# f4mpac.net
KiCad netlist of a schematic drawn in EAGLE
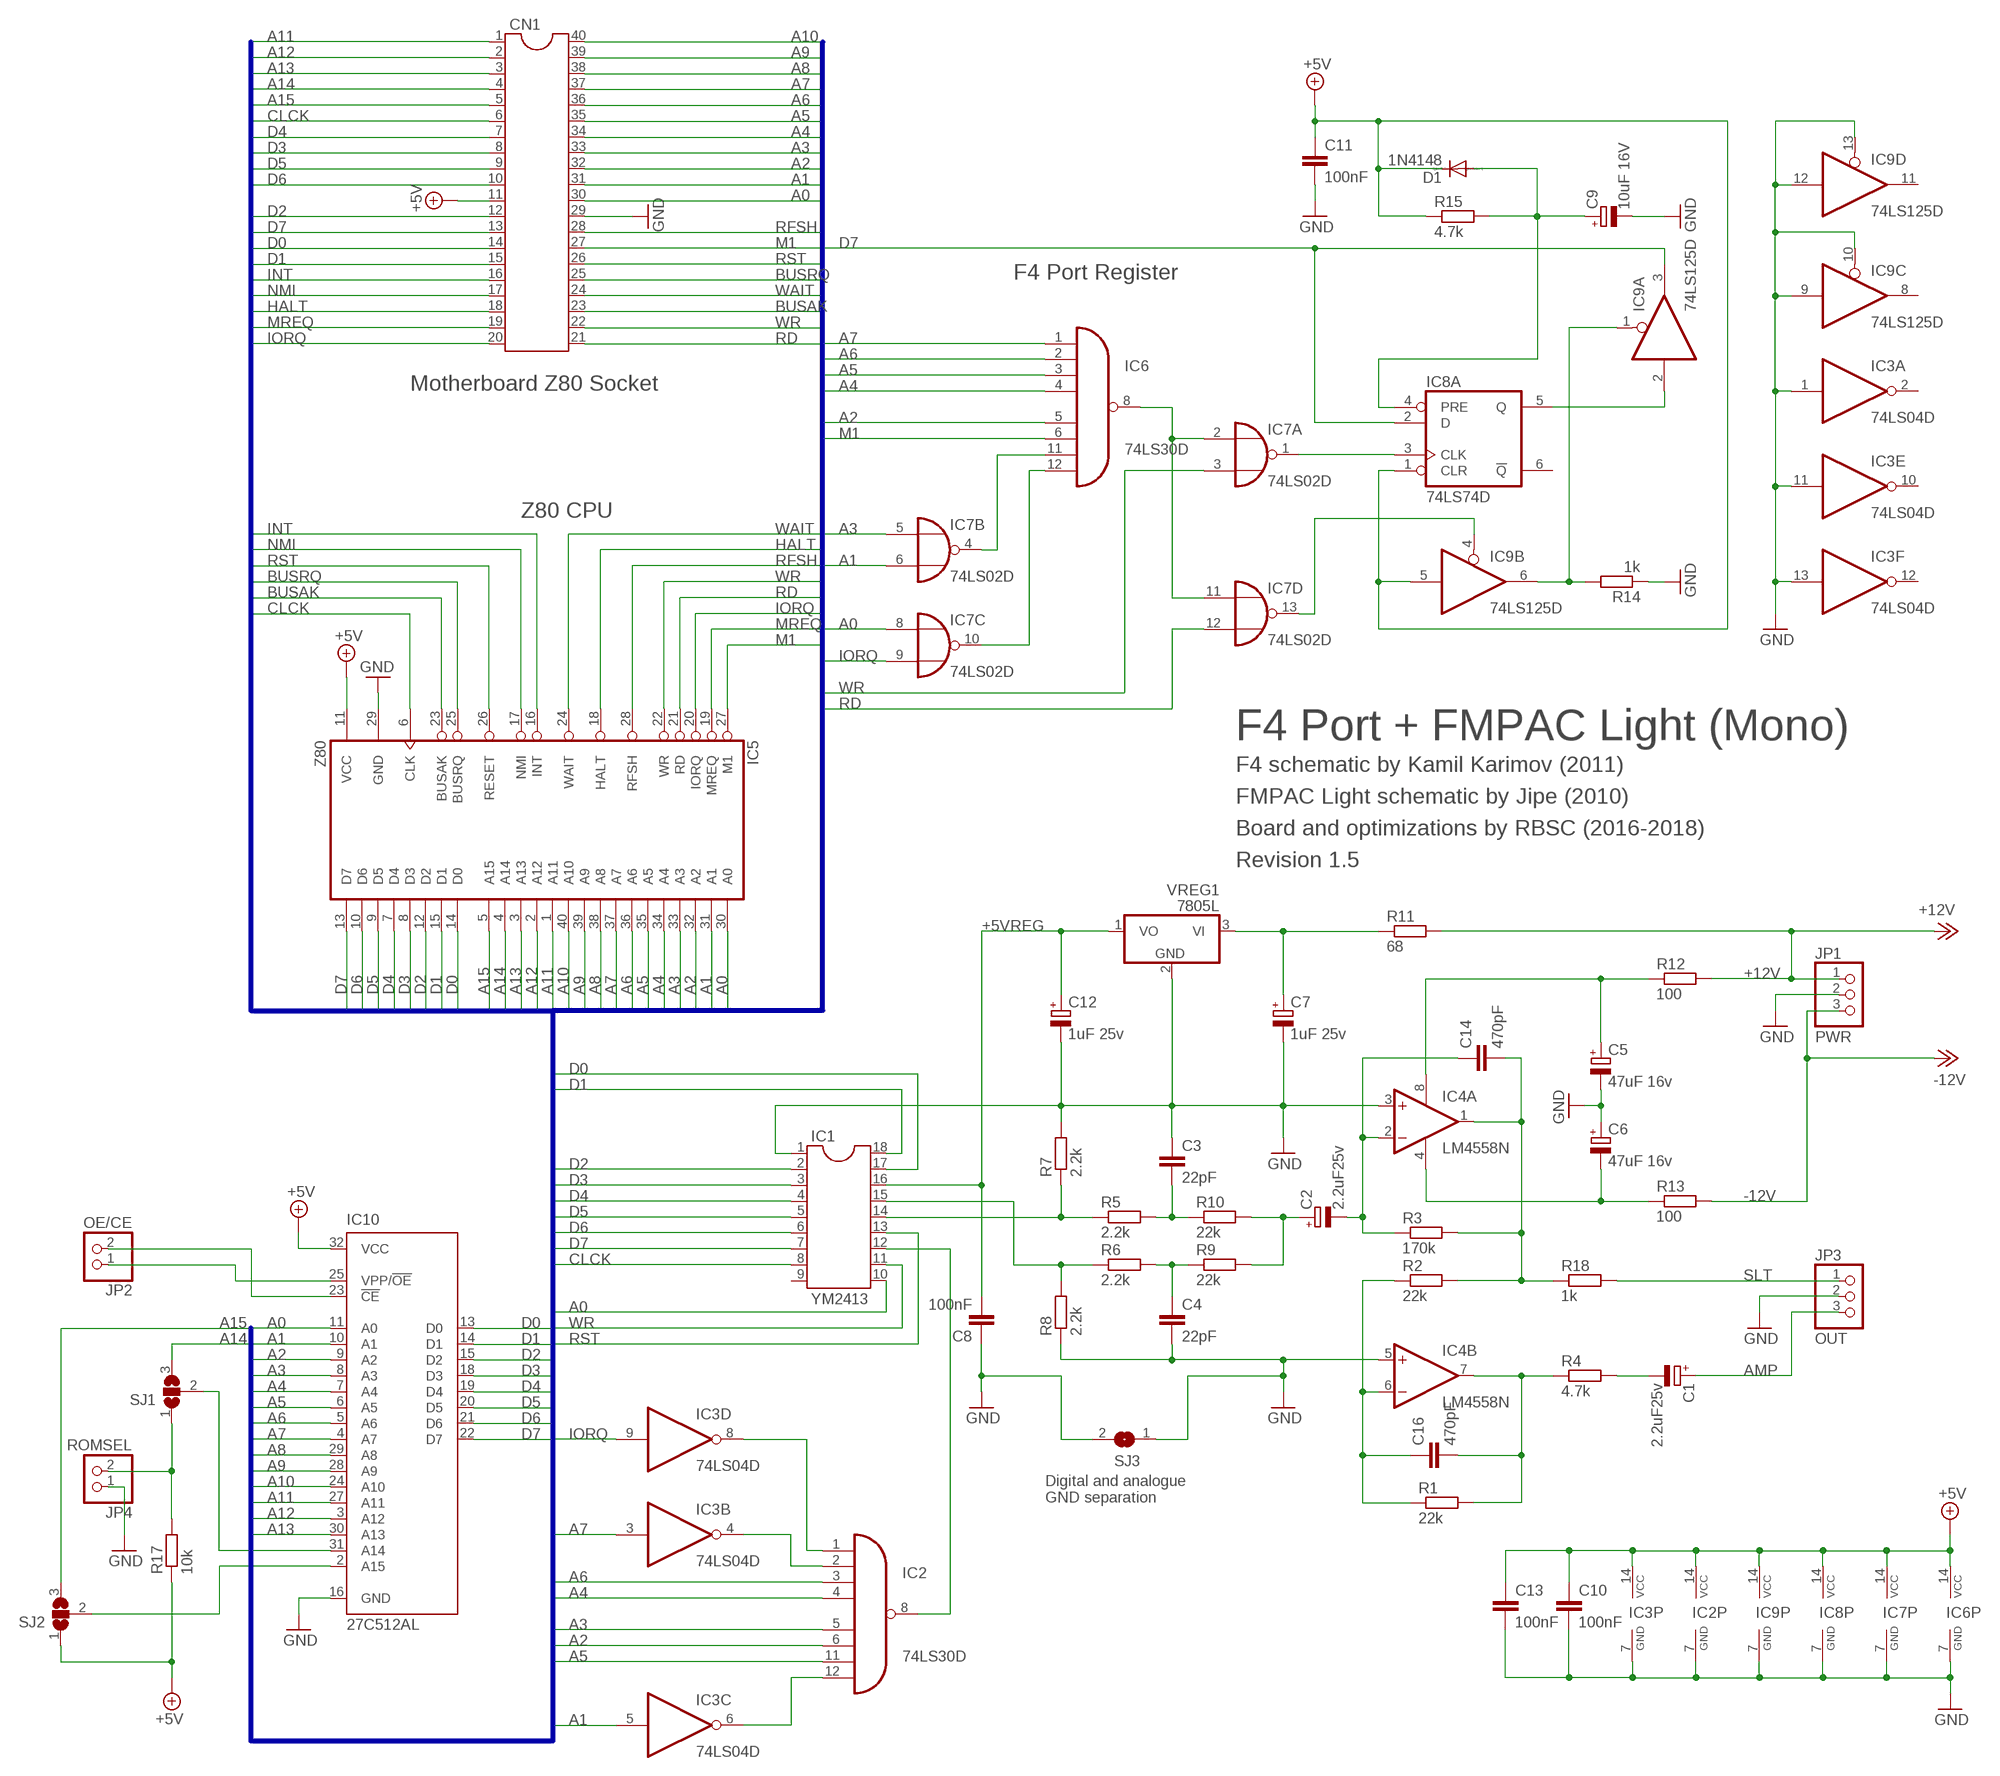
[diagram p0: schematic, sheet 1]

(export (version "E")
  (design (tool "Eeschema 10.0.6"))
  (components
    (comp (ref "C1")
      (value "2.2uF25v")
      (footprint "eagle-import:SMC_B")
      (libsource (lib "eagle-import") (part "CPOL-EUSMCB"))
    )
    (comp (ref "C2")
      (value "2.2uF25v")
      (footprint "eagle-import:SMC_B")
      (libsource (lib "eagle-import") (part "CPOL-EUSMCB"))
    )
    (comp (ref "C3")
      (value "22pF")
      (footprint "eagle-import:C0805")
      (libsource (lib "eagle-import") (part "C-EUC0805"))
    )
    (comp (ref "C4")
      (value "22pF")
      (footprint "eagle-import:C0805")
      (libsource (lib "eagle-import") (part "C-EUC0805"))
    )
    (comp (ref "C5")
      (value "47uF 16v")
      (footprint "eagle-import:SMC_C")
      (libsource (lib "eagle-import") (part "CPOL-EUSMCC"))
    )
    (comp (ref "C6")
      (value "47uF 16v")
      (footprint "eagle-import:SMC_C")
      (libsource (lib "eagle-import") (part "CPOL-EUSMCC"))
    )
    (comp (ref "C7")
      (value "1uF 25v")
      (footprint "eagle-import:SMC_B")
      (libsource (lib "eagle-import") (part "CPOL-EUSMCB"))
    )
    (comp (ref "C8")
      (value "100nF")
      (footprint "eagle-import:C0805")
      (libsource (lib "eagle-import") (part "C-EUC0805"))
    )
    (comp (ref "C9")
      (value "10uF 16V")
      (footprint "eagle-import:SMC_B")
      (libsource (lib "eagle-import") (part "CPOL-EUSMCB"))
    )
    (comp (ref "C10")
      (value "100nF")
      (footprint "eagle-import:C0805")
      (libsource (lib "eagle-import") (part "C-EUC0805"))
    )
    (comp (ref "C11")
      (value "100nF")
      (footprint "eagle-import:C0805")
      (libsource (lib "eagle-import") (part "C-EUC0805"))
    )
    (comp (ref "C12")
      (value "1uF 25v")
      (footprint "eagle-import:SMC_B")
      (libsource (lib "eagle-import") (part "CPOL-EUSMCB"))
    )
    (comp (ref "C13")
      (value "100nF")
      (footprint "eagle-import:C0805")
      (libsource (lib "eagle-import") (part "C-EUC0805"))
    )
    (comp (ref "C14")
      (value "470pF")
      (footprint "eagle-import:C0805")
      (libsource (lib "eagle-import") (part "C-EUC0805"))
    )
    (comp (ref "C16")
      (value "470pF")
      (footprint "eagle-import:C0805")
      (libsource (lib "eagle-import") (part "C-EUC0805"))
    )
    (comp (ref "CN1")
      (value "DIP40 MB CONN")
      (footprint "eagle-import:DIL40")
      (libsource (lib "eagle-import") (part "DIL40"))
    )
    (comp (ref "D1")
      (value "1N4148")
      (footprint "eagle-import:MINIMELF")
      (libsource (lib "eagle-import") (part "DIODE-MINIMELF"))
    )
    (comp (ref "IC1")
      (value "YM2413")
      (footprint "eagle-import:DIL18")
      (libsource (lib "eagle-import") (part "DIL18"))
    )
    (comp (ref "IC2")
      (value "74LS30D")
      (footprint "eagle-import:SO14")
      (libsource (lib "eagle-import") (part "7430DLS"))
    )
    (comp (ref "IC3")
      (value "74LS04D")
      (footprint "eagle-import:SO14")
      (libsource (lib "eagle-import") (part "7404DLS"))
    )
    (comp (ref "IC4")
      (value "LM4558N")
      (footprint "eagle-import:DIL08")
      (libsource (lib "eagle-import") (part "4558NLM"))
    )
    (comp (ref "IC5")
      (value "Z80")
      (footprint "eagle-import:DIL40")
      (libsource (lib "eagle-import") (part "Z80CPU"))
    )
    (comp (ref "IC6")
      (value "74LS30D")
      (footprint "eagle-import:SO14")
      (libsource (lib "eagle-import") (part "7430DLS"))
    )
    (comp (ref "IC7")
      (value "74LS02D")
      (footprint "eagle-import:SO14")
      (libsource (lib "eagle-import") (part "7402DLS"))
    )
    (comp (ref "IC8")
      (value "74LS74D")
      (footprint "eagle-import:SO14")
      (libsource (lib "eagle-import") (part "7474DLS"))
    )
    (comp (ref "IC9")
      (value "74LS125D")
      (footprint "eagle-import:SO14")
      (libsource (lib "eagle-import") (part "74125DLS"))
    )
    (comp (ref "IC10")
      (value "27C512AL")
      (footprint "eagle-import:PLCC-32")
      (fields (field (name "MPN") "M27C512-90C1"))
      (libsource (lib "eagle-import") (part "27512ALC"))
    )
    (comp (ref "JP1")
      (value "PWR")
      (footprint "eagle-import:1X03_90")
      (libsource (lib "eagle-import") (part "PINHD-1X3/90"))
    )
    (comp (ref "JP2")
      (value "OE/CE")
      (footprint "eagle-import:1X02_90")
      (libsource (lib "eagle-import") (part "PINHD-1X2/90"))
    )
    (comp (ref "JP3")
      (value "OUT")
      (footprint "eagle-import:1X03_90")
      (libsource (lib "eagle-import") (part "PINHD-1X3/90"))
    )
    (comp (ref "JP4")
      (value "ROMSEL")
      (footprint "eagle-import:1X02_90")
      (libsource (lib "eagle-import") (part "PINHD-1X2/90"))
    )
    (comp (ref "R1")
      (value "22k")
      (footprint "eagle-import:R0805")
      (libsource (lib "eagle-import") (part "R-EU_R0805"))
    )
    (comp (ref "R2")
      (value "22k")
      (footprint "eagle-import:R0805")
      (libsource (lib "eagle-import") (part "R-EU_R0805"))
    )
    (comp (ref "R3")
      (value "170k")
      (footprint "eagle-import:R0805")
      (libsource (lib "eagle-import") (part "R-EU_R0805"))
    )
    (comp (ref "R4")
      (value "4.7k")
      (footprint "eagle-import:R0805")
      (libsource (lib "eagle-import") (part "R-EU_R0805"))
    )
    (comp (ref "R5")
      (value "2.2k")
      (footprint "eagle-import:R0805")
      (libsource (lib "eagle-import") (part "R-EU_R0805"))
    )
    (comp (ref "R6")
      (value "2.2k")
      (footprint "eagle-import:R0805")
      (libsource (lib "eagle-import") (part "R-EU_R0805"))
    )
    (comp (ref "R7")
      (value "2.2k")
      (footprint "eagle-import:R0805")
      (libsource (lib "eagle-import") (part "R-EU_R0805"))
    )
    (comp (ref "R8")
      (value "2.2k")
      (footprint "eagle-import:R0805")
      (libsource (lib "eagle-import") (part "R-EU_R0805"))
    )
    (comp (ref "R9")
      (value "22k")
      (footprint "eagle-import:R0805")
      (libsource (lib "eagle-import") (part "R-EU_R0805"))
    )
    (comp (ref "R10")
      (value "22k")
      (footprint "eagle-import:R0805")
      (libsource (lib "eagle-import") (part "R-EU_R0805"))
    )
    (comp (ref "R11")
      (value "68")
      (footprint "eagle-import:R0805")
      (libsource (lib "eagle-import") (part "R-EU_R0805"))
    )
    (comp (ref "R12")
      (value "100")
      (footprint "eagle-import:R0805")
      (libsource (lib "eagle-import") (part "R-EU_R0805"))
    )
    (comp (ref "R13")
      (value "100")
      (footprint "eagle-import:R0805")
      (libsource (lib "eagle-import") (part "R-EU_R0805"))
    )
    (comp (ref "R14")
      (value "1k")
      (footprint "eagle-import:R0805")
      (libsource (lib "eagle-import") (part "R-EU_R0805"))
    )
    (comp (ref "R15")
      (value "4.7k")
      (footprint "eagle-import:M0805")
      (libsource (lib "eagle-import") (part "R-EU_M0805"))
    )
    (comp (ref "R17")
      (value "10k")
      (footprint "eagle-import:R0805")
      (libsource (lib "eagle-import") (part "R-EU_R0805"))
    )
    (comp (ref "R18")
      (value "1k")
      (footprint "eagle-import:R0805")
      (libsource (lib "eagle-import") (part "R-EU_R0805"))
    )
    (comp (ref "SJ1")
      (value "SJ2W")
      (footprint "eagle-import:SJ_2")
      (libsource (lib "eagle-import") (part "SJ2W"))
    )
    (comp (ref "SJ2")
      (value "SJ2W")
      (footprint "eagle-import:SJ_2")
      (libsource (lib "eagle-import") (part "SJ2W"))
    )
    (comp (ref "SJ3") (value "SJ") (footprint "eagle-import:SJ") (libsource (lib "eagle-import") (part "SJ")))
    (comp (ref "VREG1")
      (value "7805L")
      (footprint "eagle-import:TO92")
      (libsource (lib "eagle-import") (part "78L05"))
    )
  )
  (nets
    (net (code "1") (name "+5V") (class "Default")
      (node (ref "C10") (pin "1") (pinfunction "1_1") (pintype "passive"))
      (node (ref "C11") (pin "1") (pinfunction "1_1") (pintype "passive"))
      (node (ref "C13") (pin "1") (pinfunction "1_1") (pintype "passive"))
      (node (ref "CN1") (pin "11") (pinfunction "11_11") (pintype "passive"))
      (node (ref "D1") (pin "C") (pinfunction "C_C") (pintype "passive"))
      (node (ref "IC10") (pin "32") (pinfunction "VCC_32") (pintype "power_in"))
      (node (ref "IC2") (pin "14") (pinfunction "VCC_14") (pintype "power_in"))
      (node (ref "IC3") (pin "14") (pinfunction "VCC_14") (pintype "power_in"))
      (node (ref "IC5") (pin "11") (pinfunction "VCC_11") (pintype "power_in"))
      (node (ref "IC6") (pin "14") (pinfunction "VCC_14") (pintype "power_in"))
      (node (ref "IC7") (pin "14") (pinfunction "VCC_14") (pintype "power_in"))
      (node (ref "IC8") (pin "1") (pinfunction "CLR_1") (pintype "input"))
      (node (ref "IC8") (pin "14") (pinfunction "VCC_14") (pintype "power_in"))
      (node (ref "IC9") (pin "14") (pinfunction "VCC_14") (pintype "power_in"))
      (node (ref "IC9") (pin "5") (pinfunction "I_5") (pintype "input"))
      (node (ref "R15") (pin "1") (pinfunction "1_1") (pintype "passive"))
      (node (ref "R17") (pin "1") (pinfunction "1_1") (pintype "passive"))
      (node (ref "SJ2") (pin "1") (pinfunction "1_1") (pintype "passive"))
    )
    (net (code "2") (name "+12V") (class "Default")
      (node (ref "JP1") (pin "1") (pinfunction "1_1") (pintype "passive"))
      (node (ref "R11") (pin "2") (pinfunction "2_2") (pintype "passive"))
      (node (ref "R12") (pin "2") (pinfunction "2_2") (pintype "passive"))
    )
    (net (code "3") (name "-12V") (class "Default")
      (node (ref "JP1") (pin "3") (pinfunction "3_3") (pintype "passive"))
      (node (ref "R13") (pin "2") (pinfunction "2_2") (pintype "passive"))
    )
    (net (code "4") (name "/+5VREG") (class "Default")
      (node (ref "C12") (pin "+") (pinfunction "+_+") (pintype "passive"))
      (node (ref "C8") (pin "2") (pinfunction "2_2") (pintype "passive"))
      (node (ref "IC1") (pin "16") (pinfunction "16_16") (pintype "passive"))
      (node (ref "VREG1") (pin "1") (pinfunction "VO_1") (pintype "passive"))
    )
    (net (code "5") (name "/A0") (class "Default")
      (node (ref "CN1") (pin "30") (pinfunction "30_30") (pintype "passive"))
      (node (ref "IC1") (pin "10") (pinfunction "10_10") (pintype "passive"))
      (node (ref "IC10") (pin "11") (pinfunction "A0_11") (pintype "input"))
      (node (ref "IC5") (pin "30") (pinfunction "A0_30") (pintype "output"))
      (node (ref "IC7") (pin "8") (pinfunction "I0_8") (pintype "input"))
    )
    (net (code "6") (name "/A1") (class "Default")
      (node (ref "CN1") (pin "31") (pinfunction "31_31") (pintype "passive"))
      (node (ref "IC10") (pin "10") (pinfunction "A1_10") (pintype "input"))
      (node (ref "IC3") (pin "5") (pinfunction "I_5") (pintype "input"))
      (node (ref "IC5") (pin "31") (pinfunction "A1_31") (pintype "output"))
      (node (ref "IC7") (pin "6") (pinfunction "I1_6") (pintype "input"))
    )
    (net (code "7") (name "/A2") (class "Default")
      (node (ref "CN1") (pin "32") (pinfunction "32_32") (pintype "passive"))
      (node (ref "IC10") (pin "9") (pinfunction "A2_9") (pintype "input"))
      (node (ref "IC2") (pin "6") (pinfunction "I5_6") (pintype "input"))
      (node (ref "IC5") (pin "32") (pinfunction "A2_32") (pintype "output"))
      (node (ref "IC6") (pin "5") (pinfunction "I4_5") (pintype "input"))
    )
    (net (code "8") (name "/A3") (class "Default")
      (node (ref "CN1") (pin "33") (pinfunction "33_33") (pintype "passive"))
      (node (ref "IC10") (pin "8") (pinfunction "A3_8") (pintype "input"))
      (node (ref "IC2") (pin "5") (pinfunction "I4_5") (pintype "input"))
      (node (ref "IC5") (pin "33") (pinfunction "A3_33") (pintype "output"))
      (node (ref "IC7") (pin "5") (pinfunction "I0_5") (pintype "input"))
    )
    (net (code "9") (name "/A4") (class "Default")
      (node (ref "CN1") (pin "34") (pinfunction "34_34") (pintype "passive"))
      (node (ref "IC10") (pin "7") (pinfunction "A4_7") (pintype "input"))
      (node (ref "IC2") (pin "4") (pinfunction "I3_4") (pintype "input"))
      (node (ref "IC5") (pin "34") (pinfunction "A4_34") (pintype "output"))
      (node (ref "IC6") (pin "4") (pinfunction "I3_4") (pintype "input"))
    )
    (net (code "10") (name "/A5") (class "Default")
      (node (ref "CN1") (pin "35") (pinfunction "35_35") (pintype "passive"))
      (node (ref "IC10") (pin "6") (pinfunction "A5_6") (pintype "input"))
      (node (ref "IC2") (pin "11") (pinfunction "I6_11") (pintype "input"))
      (node (ref "IC5") (pin "35") (pinfunction "A5_35") (pintype "output"))
      (node (ref "IC6") (pin "3") (pinfunction "I2_3") (pintype "input"))
    )
    (net (code "11") (name "/A6") (class "Default")
      (node (ref "CN1") (pin "36") (pinfunction "36_36") (pintype "passive"))
      (node (ref "IC10") (pin "5") (pinfunction "A6_5") (pintype "input"))
      (node (ref "IC2") (pin "3") (pinfunction "I2_3") (pintype "input"))
      (node (ref "IC5") (pin "36") (pinfunction "A6_36") (pintype "output"))
      (node (ref "IC6") (pin "2") (pinfunction "I1_2") (pintype "input"))
    )
    (net (code "12") (name "/A7") (class "Default")
      (node (ref "CN1") (pin "37") (pinfunction "37_37") (pintype "passive"))
      (node (ref "IC10") (pin "4") (pinfunction "A7_4") (pintype "input"))
      (node (ref "IC3") (pin "3") (pinfunction "I_3") (pintype "input"))
      (node (ref "IC5") (pin "37") (pinfunction "A7_37") (pintype "output"))
      (node (ref "IC6") (pin "1") (pinfunction "I0_1") (pintype "input"))
    )
    (net (code "13") (name "/A8") (class "Default")
      (node (ref "CN1") (pin "38") (pinfunction "38_38") (pintype "passive"))
      (node (ref "IC10") (pin "29") (pinfunction "A8_29") (pintype "input"))
      (node (ref "IC5") (pin "38") (pinfunction "A8_38") (pintype "output"))
    )
    (net (code "14") (name "/A9") (class "Default")
      (node (ref "CN1") (pin "39") (pinfunction "39_39") (pintype "passive"))
      (node (ref "IC10") (pin "28") (pinfunction "A9_28") (pintype "input"))
      (node (ref "IC5") (pin "39") (pinfunction "A9_39") (pintype "output"))
    )
    (net (code "15") (name "/A10") (class "Default")
      (node (ref "CN1") (pin "40") (pinfunction "40_40") (pintype "passive"))
      (node (ref "IC10") (pin "24") (pinfunction "A10_24") (pintype "input"))
      (node (ref "IC5") (pin "40") (pinfunction "A10_40") (pintype "output"))
    )
    (net (code "16") (name "/A11") (class "Default")
      (node (ref "CN1") (pin "1") (pinfunction "1_1") (pintype "passive"))
      (node (ref "IC10") (pin "27") (pinfunction "A11_27") (pintype "input"))
      (node (ref "IC5") (pin "1") (pinfunction "A11_1") (pintype "output"))
    )
    (net (code "17") (name "/A12") (class "Default")
      (node (ref "CN1") (pin "2") (pinfunction "2_2") (pintype "passive"))
      (node (ref "IC10") (pin "3") (pinfunction "A12_3") (pintype "input"))
      (node (ref "IC5") (pin "2") (pinfunction "A12_2") (pintype "output"))
    )
    (net (code "18") (name "/A13") (class "Default")
      (node (ref "CN1") (pin "3") (pinfunction "3_3") (pintype "passive"))
      (node (ref "IC10") (pin "30") (pinfunction "A13_30") (pintype "input"))
      (node (ref "IC5") (pin "3") (pinfunction "A13_3") (pintype "output"))
    )
    (net (code "19") (name "/A14") (class "Default")
      (node (ref "CN1") (pin "4") (pinfunction "4_4") (pintype "passive"))
      (node (ref "IC5") (pin "4") (pinfunction "A14_4") (pintype "output"))
      (node (ref "SJ1") (pin "3") (pinfunction "3_3") (pintype "passive"))
    )
    (net (code "20") (name "/A15") (class "Default")
      (node (ref "CN1") (pin "5") (pinfunction "5_5") (pintype "passive"))
      (node (ref "IC5") (pin "5") (pinfunction "A15_5") (pintype "output"))
      (node (ref "SJ2") (pin "3") (pinfunction "3_3") (pintype "passive"))
    )
    (net (code "21") (name "/AMP") (class "Default")
      (node (ref "C1") (pin "+") (pinfunction "+_+") (pintype "passive"))
      (node (ref "JP3") (pin "3") (pinfunction "3_3") (pintype "passive"))
    )
    (net (code "22") (name "/BUSAK") (class "Default")
      (node (ref "CN1") (pin "23") (pinfunction "23_23") (pintype "passive"))
      (node (ref "IC5") (pin "23") (pinfunction "BUSAK_23") (pintype "output"))
    )
    (net (code "23") (name "/BUSRQ") (class "Default")
      (node (ref "CN1") (pin "25") (pinfunction "25_25") (pintype "passive"))
      (node (ref "IC5") (pin "25") (pinfunction "BUSRQ_25") (pintype "input"))
    )
    (net (code "24") (name "/CLCK") (class "Default")
      (node (ref "CN1") (pin "6") (pinfunction "6_6") (pintype "passive"))
      (node (ref "IC1") (pin "8") (pinfunction "8_8") (pintype "passive"))
      (node (ref "IC5") (pin "6") (pinfunction "CLK_6") (pintype "input"))
    )
    (net (code "25") (name "/D0") (class "Default")
      (node (ref "CN1") (pin "14") (pinfunction "14_14") (pintype "passive"))
      (node (ref "IC1") (pin "17") (pinfunction "17_17") (pintype "passive"))
      (node (ref "IC10") (pin "13") (pinfunction "D0_13") (pintype "tri_state"))
      (node (ref "IC5") (pin "14") (pinfunction "D0_14") (pintype "bidirectional"))
    )
    (net (code "26") (name "/D1") (class "Default")
      (node (ref "CN1") (pin "15") (pinfunction "15_15") (pintype "passive"))
      (node (ref "IC1") (pin "18") (pinfunction "18_18") (pintype "passive"))
      (node (ref "IC10") (pin "14") (pinfunction "D1_14") (pintype "tri_state"))
      (node (ref "IC5") (pin "15") (pinfunction "D1_15") (pintype "bidirectional"))
    )
    (net (code "27") (name "/D2") (class "Default")
      (node (ref "CN1") (pin "12") (pinfunction "12_12") (pintype "passive"))
      (node (ref "IC1") (pin "2") (pinfunction "2_2") (pintype "passive"))
      (node (ref "IC10") (pin "15") (pinfunction "D2_15") (pintype "tri_state"))
      (node (ref "IC5") (pin "12") (pinfunction "D2_12") (pintype "bidirectional"))
    )
    (net (code "28") (name "/D3") (class "Default")
      (node (ref "CN1") (pin "8") (pinfunction "8_8") (pintype "passive"))
      (node (ref "IC1") (pin "3") (pinfunction "3_3") (pintype "passive"))
      (node (ref "IC10") (pin "18") (pinfunction "D3_18") (pintype "tri_state"))
      (node (ref "IC5") (pin "8") (pinfunction "D3_8") (pintype "bidirectional"))
    )
    (net (code "29") (name "/D4") (class "Default")
      (node (ref "CN1") (pin "7") (pinfunction "7_7") (pintype "passive"))
      (node (ref "IC1") (pin "4") (pinfunction "4_4") (pintype "passive"))
      (node (ref "IC10") (pin "19") (pinfunction "D4_19") (pintype "tri_state"))
      (node (ref "IC5") (pin "7") (pinfunction "D4_7") (pintype "bidirectional"))
    )
    (net (code "30") (name "/D5") (class "Default")
      (node (ref "CN1") (pin "9") (pinfunction "9_9") (pintype "passive"))
      (node (ref "IC1") (pin "5") (pinfunction "5_5") (pintype "passive"))
      (node (ref "IC10") (pin "20") (pinfunction "D5_20") (pintype "tri_state"))
      (node (ref "IC5") (pin "9") (pinfunction "D5_9") (pintype "bidirectional"))
    )
    (net (code "31") (name "/D6") (class "Default")
      (node (ref "CN1") (pin "10") (pinfunction "10_10") (pintype "passive"))
      (node (ref "IC1") (pin "6") (pinfunction "6_6") (pintype "passive"))
      (node (ref "IC10") (pin "21") (pinfunction "D6_21") (pintype "tri_state"))
      (node (ref "IC5") (pin "10") (pinfunction "D6_10") (pintype "bidirectional"))
    )
    (net (code "32") (name "/D7") (class "Default")
      (node (ref "CN1") (pin "13") (pinfunction "13_13") (pintype "passive"))
      (node (ref "IC1") (pin "7") (pinfunction "7_7") (pintype "passive"))
      (node (ref "IC10") (pin "22") (pinfunction "D7_22") (pintype "tri_state"))
      (node (ref "IC5") (pin "13") (pinfunction "D7_13") (pintype "bidirectional"))
      (node (ref "IC8") (pin "2") (pinfunction "D_2") (pintype "input"))
      (node (ref "IC9") (pin "3") (pinfunction "O_3") (pintype "tri_state"))
    )
    (net (code "33") (name "/HALT") (class "Default")
      (node (ref "CN1") (pin "18") (pinfunction "18_18") (pintype "passive"))
      (node (ref "IC5") (pin "18") (pinfunction "HALT_18") (pintype "output"))
    )
    (net (code "34") (name "/INT") (class "Default")
      (node (ref "CN1") (pin "16") (pinfunction "16_16") (pintype "passive"))
      (node (ref "IC5") (pin "16") (pinfunction "INT_16") (pintype "input"))
    )
    (net (code "35") (name "/IORQ") (class "Default")
      (node (ref "CN1") (pin "20") (pinfunction "20_20") (pintype "passive"))
      (node (ref "IC3") (pin "9") (pinfunction "I_9") (pintype "input"))
      (node (ref "IC5") (pin "20") (pinfunction "IORQ_20") (pintype "output"))
      (node (ref "IC7") (pin "9") (pinfunction "I1_9") (pintype "input"))
    )
    (net (code "36") (name "/M1") (class "Default")
      (node (ref "CN1") (pin "27") (pinfunction "27_27") (pintype "passive"))
      (node (ref "IC5") (pin "27") (pinfunction "M1_27") (pintype "output"))
      (node (ref "IC6") (pin "6") (pinfunction "I5_6") (pintype "input"))
    )
    (net (code "37") (name "/MREQ") (class "Default")
      (node (ref "CN1") (pin "19") (pinfunction "19_19") (pintype "passive"))
      (node (ref "IC5") (pin "19") (pinfunction "MREQ_19") (pintype "output"))
    )
    (net (code "38") (name "/NMI") (class "Default")
      (node (ref "CN1") (pin "17") (pinfunction "17_17") (pintype "passive"))
      (node (ref "IC5") (pin "17") (pinfunction "NMI_17") (pintype "input"))
    )
    (net (code "39") (name "/RD") (class "Default")
      (node (ref "CN1") (pin "21") (pinfunction "21_21") (pintype "passive"))
      (node (ref "IC5") (pin "21") (pinfunction "RD_21") (pintype "output"))
      (node (ref "IC7") (pin "12") (pinfunction "I1_12") (pintype "input"))
    )
    (net (code "40") (name "/RFSH") (class "Default")
      (node (ref "CN1") (pin "28") (pinfunction "28_28") (pintype "passive"))
      (node (ref "IC5") (pin "28") (pinfunction "RFSH_28") (pintype "output"))
    )
    (net (code "41") (name "/RST") (class "Default")
      (node (ref "CN1") (pin "26") (pinfunction "26_26") (pintype "passive"))
      (node (ref "IC1") (pin "13") (pinfunction "13_13") (pintype "passive"))
      (node (ref "IC5") (pin "26") (pinfunction "RESET_26") (pintype "input"))
    )
    (net (code "42") (name "/SLT") (class "Default")
      (node (ref "JP3") (pin "1") (pinfunction "1_1") (pintype "passive"))
      (node (ref "R18") (pin "2") (pinfunction "2_2") (pintype "passive"))
    )
    (net (code "43") (name "/WAIT") (class "Default")
      (node (ref "CN1") (pin "24") (pinfunction "24_24") (pintype "passive"))
      (node (ref "IC5") (pin "24") (pinfunction "WAIT_24") (pintype "input"))
    )
    (net (code "44") (name "/WR") (class "Default")
      (node (ref "CN1") (pin "22") (pinfunction "22_22") (pintype "passive"))
      (node (ref "IC1") (pin "11") (pinfunction "11_11") (pintype "passive"))
      (node (ref "IC5") (pin "22") (pinfunction "WR_22") (pintype "output"))
      (node (ref "IC7") (pin "3") (pinfunction "I1_3") (pintype "input"))
    )
    (net (code "45") (name "GND") (class "Default")
      (node (ref "C10") (pin "2") (pinfunction "2_2") (pintype "passive"))
      (node (ref "C11") (pin "2") (pinfunction "2_2") (pintype "passive"))
      (node (ref "C12") (pin "-") (pinfunction "-_-") (pintype "passive"))
      (node (ref "C13") (pin "2") (pinfunction "2_2") (pintype "passive"))
      (node (ref "C3") (pin "1") (pinfunction "1_1") (pintype "passive"))
      (node (ref "C4") (pin "2") (pinfunction "2_2") (pintype "passive"))
      (node (ref "C5") (pin "-") (pinfunction "-_-") (pintype "passive"))
      (node (ref "C6") (pin "+") (pinfunction "+_+") (pintype "passive"))
      (node (ref "C7") (pin "-") (pinfunction "-_-") (pintype "passive"))
      (node (ref "C8") (pin "1") (pinfunction "1_1") (pintype "passive"))
      (node (ref "C9") (pin "-") (pinfunction "-_-") (pintype "passive"))
      (node (ref "CN1") (pin "29") (pinfunction "29_29") (pintype "passive"))
      (node (ref "IC1") (pin "1") (pinfunction "1_1") (pintype "passive"))
      (node (ref "IC10") (pin "16") (pinfunction "GND_16") (pintype "power_in"))
      (node (ref "IC2") (pin "7") (pinfunction "GND_7") (pintype "power_in"))
      (node (ref "IC3") (pin "1") (pinfunction "I_1") (pintype "input"))
      (node (ref "IC3") (pin "11") (pinfunction "I_11") (pintype "input"))
      (node (ref "IC3") (pin "13") (pinfunction "I_13") (pintype "input"))
      (node (ref "IC3") (pin "7") (pinfunction "GND_7") (pintype "power_in"))
      (node (ref "IC4") (pin "3") (pinfunction "+IN_3") (pintype "input"))
      (node (ref "IC4") (pin "5") (pinfunction "+IN_5") (pintype "input"))
      (node (ref "IC5") (pin "29") (pinfunction "GND_29") (pintype "power_in"))
      (node (ref "IC6") (pin "7") (pinfunction "GND_7") (pintype "power_in"))
      (node (ref "IC7") (pin "7") (pinfunction "GND_7") (pintype "power_in"))
      (node (ref "IC8") (pin "7") (pinfunction "GND_7") (pintype "power_in"))
      (node (ref "IC9") (pin "10") (pinfunction "OE_10") (pintype "input"))
      (node (ref "IC9") (pin "12") (pinfunction "I_12") (pintype "input"))
      (node (ref "IC9") (pin "13") (pinfunction "OE_13") (pintype "input"))
      (node (ref "IC9") (pin "7") (pinfunction "GND_7") (pintype "power_in"))
      (node (ref "IC9") (pin "9") (pinfunction "I_9") (pintype "input"))
      (node (ref "JP1") (pin "2") (pinfunction "2_2") (pintype "passive"))
      (node (ref "JP3") (pin "2") (pinfunction "2_2") (pintype "passive"))
      (node (ref "JP4") (pin "1") (pinfunction "1_1") (pintype "passive"))
      (node (ref "R14") (pin "1") (pinfunction "1_1") (pintype "passive"))
      (node (ref "R7") (pin "2") (pinfunction "2_2") (pintype "passive"))
      (node (ref "R8") (pin "1") (pinfunction "1_1") (pintype "passive"))
      (node (ref "SJ3") (pin "1") (pinfunction "1_1") (pintype "passive"))
      (node (ref "SJ3") (pin "2") (pinfunction "2_2") (pintype "passive"))
      (node (ref "VREG1") (pin "2") (pinfunction "GND_2") (pintype "passive"))
    )
    (net (code "46") (name "Net-(C1-Pad-)") (class "Default")
      (node (ref "C1") (pin "-") (pinfunction "-_-") (pintype "passive"))
      (node (ref "R4") (pin "2") (pinfunction "2_2") (pintype "passive"))
    )
    (net (code "47") (name "Net-(C2-Pad+)") (class "Default")
      (node (ref "C2") (pin "+") (pinfunction "+_+") (pintype "passive"))
      (node (ref "R10") (pin "2") (pinfunction "2_2") (pintype "passive"))
      (node (ref "R9") (pin "2") (pinfunction "2_2") (pintype "passive"))
    )
    (net (code "48") (name "Net-(C3-Pad2)") (class "Default")
      (node (ref "C3") (pin "2") (pinfunction "2_2") (pintype "passive"))
      (node (ref "R10") (pin "1") (pinfunction "1_1") (pintype "passive"))
      (node (ref "R5") (pin "2") (pinfunction "2_2") (pintype "passive"))
    )
    (net (code "49") (name "Net-(C4-Pad1)") (class "Default")
      (node (ref "C4") (pin "1") (pinfunction "1_1") (pintype "passive"))
      (node (ref "R6") (pin "2") (pinfunction "2_2") (pintype "passive"))
      (node (ref "R9") (pin "1") (pinfunction "1_1") (pintype "passive"))
    )
    (net (code "50") (name "Net-(IC1-Pad14)") (class "Default")
      (node (ref "IC1") (pin "14") (pinfunction "14_14") (pintype "passive"))
      (node (ref "R5") (pin "1") (pinfunction "1_1") (pintype "passive"))
      (node (ref "R7") (pin "1") (pinfunction "1_1") (pintype "passive"))
    )
    (net (code "51") (name "Net-(IC1-Pad15)") (class "Default")
      (node (ref "IC1") (pin "15") (pinfunction "15_15") (pintype "passive"))
      (node (ref "R6") (pin "1") (pinfunction "1_1") (pintype "passive"))
      (node (ref "R8") (pin "2") (pinfunction "2_2") (pintype "passive"))
    )
    (net (code "52") (name "Net-(IC2A-I0)") (class "Default")
      (node (ref "IC2") (pin "1") (pinfunction "I0_1") (pintype "input"))
      (node (ref "IC3") (pin "8") (pinfunction "O_8") (pintype "output"))
    )
    (net (code "53") (name "Net-(IC2A-I1)") (class "Default")
      (node (ref "IC2") (pin "2") (pinfunction "I1_2") (pintype "input"))
      (node (ref "IC3") (pin "4") (pinfunction "O_4") (pintype "output"))
    )
    (net (code "54") (name "Net-(IC2A-I7)") (class "Default")
      (node (ref "IC2") (pin "12") (pinfunction "I7_12") (pintype "input"))
      (node (ref "IC3") (pin "6") (pinfunction "O_6") (pintype "output"))
    )
    (net (code "55") (name "Net-(IC2A-O)") (class "Default")
      (node (ref "IC1") (pin "12") (pinfunction "12_12") (pintype "passive"))
      (node (ref "IC2") (pin "8") (pinfunction "O_8") (pintype "output"))
    )
    (net (code "56") (name "Net-(IC4A--IN)") (class "Default")
      (node (ref "C14") (pin "1") (pinfunction "1_1") (pintype "passive"))
      (node (ref "C2") (pin "-") (pinfunction "-_-") (pintype "passive"))
      (node (ref "IC4") (pin "2") (pinfunction "-IN_2") (pintype "input"))
      (node (ref "R3") (pin "1") (pinfunction "1_1") (pintype "passive"))
    )
    (net (code "57") (name "Net-(IC4A-OUT)") (class "Default")
      (node (ref "C14") (pin "2") (pinfunction "2_2") (pintype "passive"))
      (node (ref "IC4") (pin "1") (pinfunction "OUT_1") (pintype "output"))
      (node (ref "R18") (pin "1") (pinfunction "1_1") (pintype "passive"))
      (node (ref "R2") (pin "2") (pinfunction "2_2") (pintype "passive"))
      (node (ref "R3") (pin "2") (pinfunction "2_2") (pintype "passive"))
    )
    (net (code "58") (name "Net-(IC4B--IN)") (class "Default")
      (node (ref "C16") (pin "1") (pinfunction "1_1") (pintype "passive"))
      (node (ref "IC4") (pin "6") (pinfunction "-IN_6") (pintype "input"))
      (node (ref "R1") (pin "1") (pinfunction "1_1") (pintype "passive"))
      (node (ref "R2") (pin "1") (pinfunction "1_1") (pintype "passive"))
    )
    (net (code "59") (name "Net-(IC4B-OUT)") (class "Default")
      (node (ref "C16") (pin "2") (pinfunction "2_2") (pintype "passive"))
      (node (ref "IC4") (pin "7") (pinfunction "OUT_7") (pintype "output"))
      (node (ref "R1") (pin "2") (pinfunction "2_2") (pintype "passive"))
      (node (ref "R4") (pin "1") (pinfunction "1_1") (pintype "passive"))
    )
    (net (code "60") (name "Net-(IC4C-V+)") (class "Default")
      (node (ref "C5") (pin "+") (pinfunction "+_+") (pintype "passive"))
      (node (ref "IC4") (pin "8") (pinfunction "V+_8") (pintype "power_in"))
      (node (ref "R12") (pin "1") (pinfunction "1_1") (pintype "passive"))
    )
    (net (code "61") (name "Net-(IC4C-V-)") (class "Default")
      (node (ref "C6") (pin "-") (pinfunction "-_-") (pintype "passive"))
      (node (ref "IC4") (pin "4") (pinfunction "V-_4") (pintype "power_in"))
      (node (ref "R13") (pin "1") (pinfunction "1_1") (pintype "passive"))
    )
    (net (code "62") (name "Net-(IC6A-I6)") (class "Default")
      (node (ref "IC6") (pin "11") (pinfunction "I6_11") (pintype "input"))
      (node (ref "IC7") (pin "4") (pinfunction "O_4") (pintype "output"))
    )
    (net (code "63") (name "Net-(IC6A-I7)") (class "Default")
      (node (ref "IC6") (pin "12") (pinfunction "I7_12") (pintype "input"))
      (node (ref "IC7") (pin "10") (pinfunction "O_10") (pintype "output"))
    )
    (net (code "64") (name "Net-(IC6A-O)") (class "Default")
      (node (ref "IC6") (pin "8") (pinfunction "O_8") (pintype "output"))
      (node (ref "IC7") (pin "11") (pinfunction "I0_11") (pintype "input"))
      (node (ref "IC7") (pin "2") (pinfunction "I0_2") (pintype "input"))
    )
    (net (code "65") (name "Net-(IC7A-O)") (class "Default")
      (node (ref "IC7") (pin "1") (pinfunction "O_1") (pintype "output"))
      (node (ref "IC8") (pin "3") (pinfunction "CLK_3") (pintype "input"))
    )
    (net (code "66") (name "Net-(IC7D-O)") (class "Default")
      (node (ref "IC7") (pin "13") (pinfunction "O_13") (pintype "output"))
      (node (ref "IC9") (pin "4") (pinfunction "OE_4") (pintype "input"))
    )
    (net (code "67") (name "Net-(IC8A-PRE)") (class "Default")
      (node (ref "C9") (pin "+") (pinfunction "+_+") (pintype "passive"))
      (node (ref "D1") (pin "A") (pinfunction "A_A") (pintype "passive"))
      (node (ref "IC8") (pin "4") (pinfunction "PRE_4") (pintype "input"))
      (node (ref "R15") (pin "2") (pinfunction "2_2") (pintype "passive"))
    )
    (net (code "68") (name "Net-(IC8A-Q)") (class "Default")
      (node (ref "IC8") (pin "5") (pinfunction "Q_5") (pintype "output"))
      (node (ref "IC9") (pin "2") (pinfunction "I_2") (pintype "input"))
    )
    (net (code "69") (name "Net-(IC9A-OE)") (class "Default")
      (node (ref "IC9") (pin "1") (pinfunction "OE_1") (pintype "input"))
      (node (ref "IC9") (pin "6") (pinfunction "O_6") (pintype "tri_state"))
      (node (ref "R14") (pin "2") (pinfunction "2_2") (pintype "passive"))
    )
    (net (code "70") (name "Net-(IC10-A14)") (class "Default")
      (node (ref "IC10") (pin "31") (pinfunction "A14_31") (pintype "input"))
      (node (ref "SJ1") (pin "2") (pinfunction "2_2") (pintype "passive"))
    )
    (net (code "71") (name "Net-(IC10-A15)") (class "Default")
      (node (ref "IC10") (pin "2") (pinfunction "A15_2") (pintype "input"))
      (node (ref "SJ2") (pin "2") (pinfunction "2_2") (pintype "passive"))
    )
    (net (code "72") (name "Net-(IC10-VPP{slash}~{OE})") (class "Default")
      (node (ref "IC10") (pin "25") (pinfunction "VPP/~{OE}_25") (pintype "input"))
      (node (ref "JP2") (pin "1") (pinfunction "1_1") (pintype "passive"))
    )
    (net (code "73") (name "Net-(IC10-~{CE})") (class "Default")
      (node (ref "IC10") (pin "23") (pinfunction "~{CE}_23") (pintype "input"))
      (node (ref "JP2") (pin "2") (pinfunction "2_2") (pintype "passive"))
    )
    (net (code "74") (name "Net-(JP4-Pad2)") (class "Default")
      (node (ref "JP4") (pin "2") (pinfunction "2_2") (pintype "passive"))
      (node (ref "R17") (pin "2") (pinfunction "2_2") (pintype "passive"))
      (node (ref "SJ1") (pin "1") (pinfunction "1_1") (pintype "passive"))
    )
    (net (code "75") (name "Net-(VREG1-VI)") (class "Default")
      (node (ref "C7") (pin "+") (pinfunction "+_+") (pintype "passive"))
      (node (ref "R11") (pin "1") (pinfunction "1_1") (pintype "passive"))
      (node (ref "VREG1") (pin "3") (pinfunction "VI_3") (pintype "input"))
    )
    (net (code "76") (name "unconnected-(IC1-Pad9)") (class "Default")
      (node (ref "IC1") (pin "9") (pinfunction "9_9") (pintype "passive"))
    )
    (net (code "77") (name "unconnected-(IC3A-O-Pad2)") (class "Default")
      (node (ref "IC3") (pin "2") (pinfunction "O_2") (pintype "output"))
    )
    (net (code "78") (name "unconnected-(IC3E-O-Pad10)") (class "Default")
      (node (ref "IC3") (pin "10") (pinfunction "O_10") (pintype "output"))
    )
    (net (code "79") (name "unconnected-(IC3F-O-Pad12)") (class "Default")
      (node (ref "IC3") (pin "12") (pinfunction "O_12") (pintype "output"))
    )
    (net (code "80") (name "unconnected-(IC8A-~{Q}-Pad6)") (class "Default")
      (node (ref "IC8") (pin "6") (pinfunction "~{Q}_6") (pintype "output"))
    )
    (net (code "81") (name "unconnected-(IC9C-O-Pad8)") (class "Default")
      (node (ref "IC9") (pin "8") (pinfunction "O_8") (pintype "tri_state"))
    )
    (net (code "82") (name "unconnected-(IC9D-O-Pad11)") (class "Default")
      (node (ref "IC9") (pin "11") (pinfunction "O_11") (pintype "tri_state"))
    )
  )
)
